# USB.net
KiCad netlist of a schematic drawn in Altium Designer
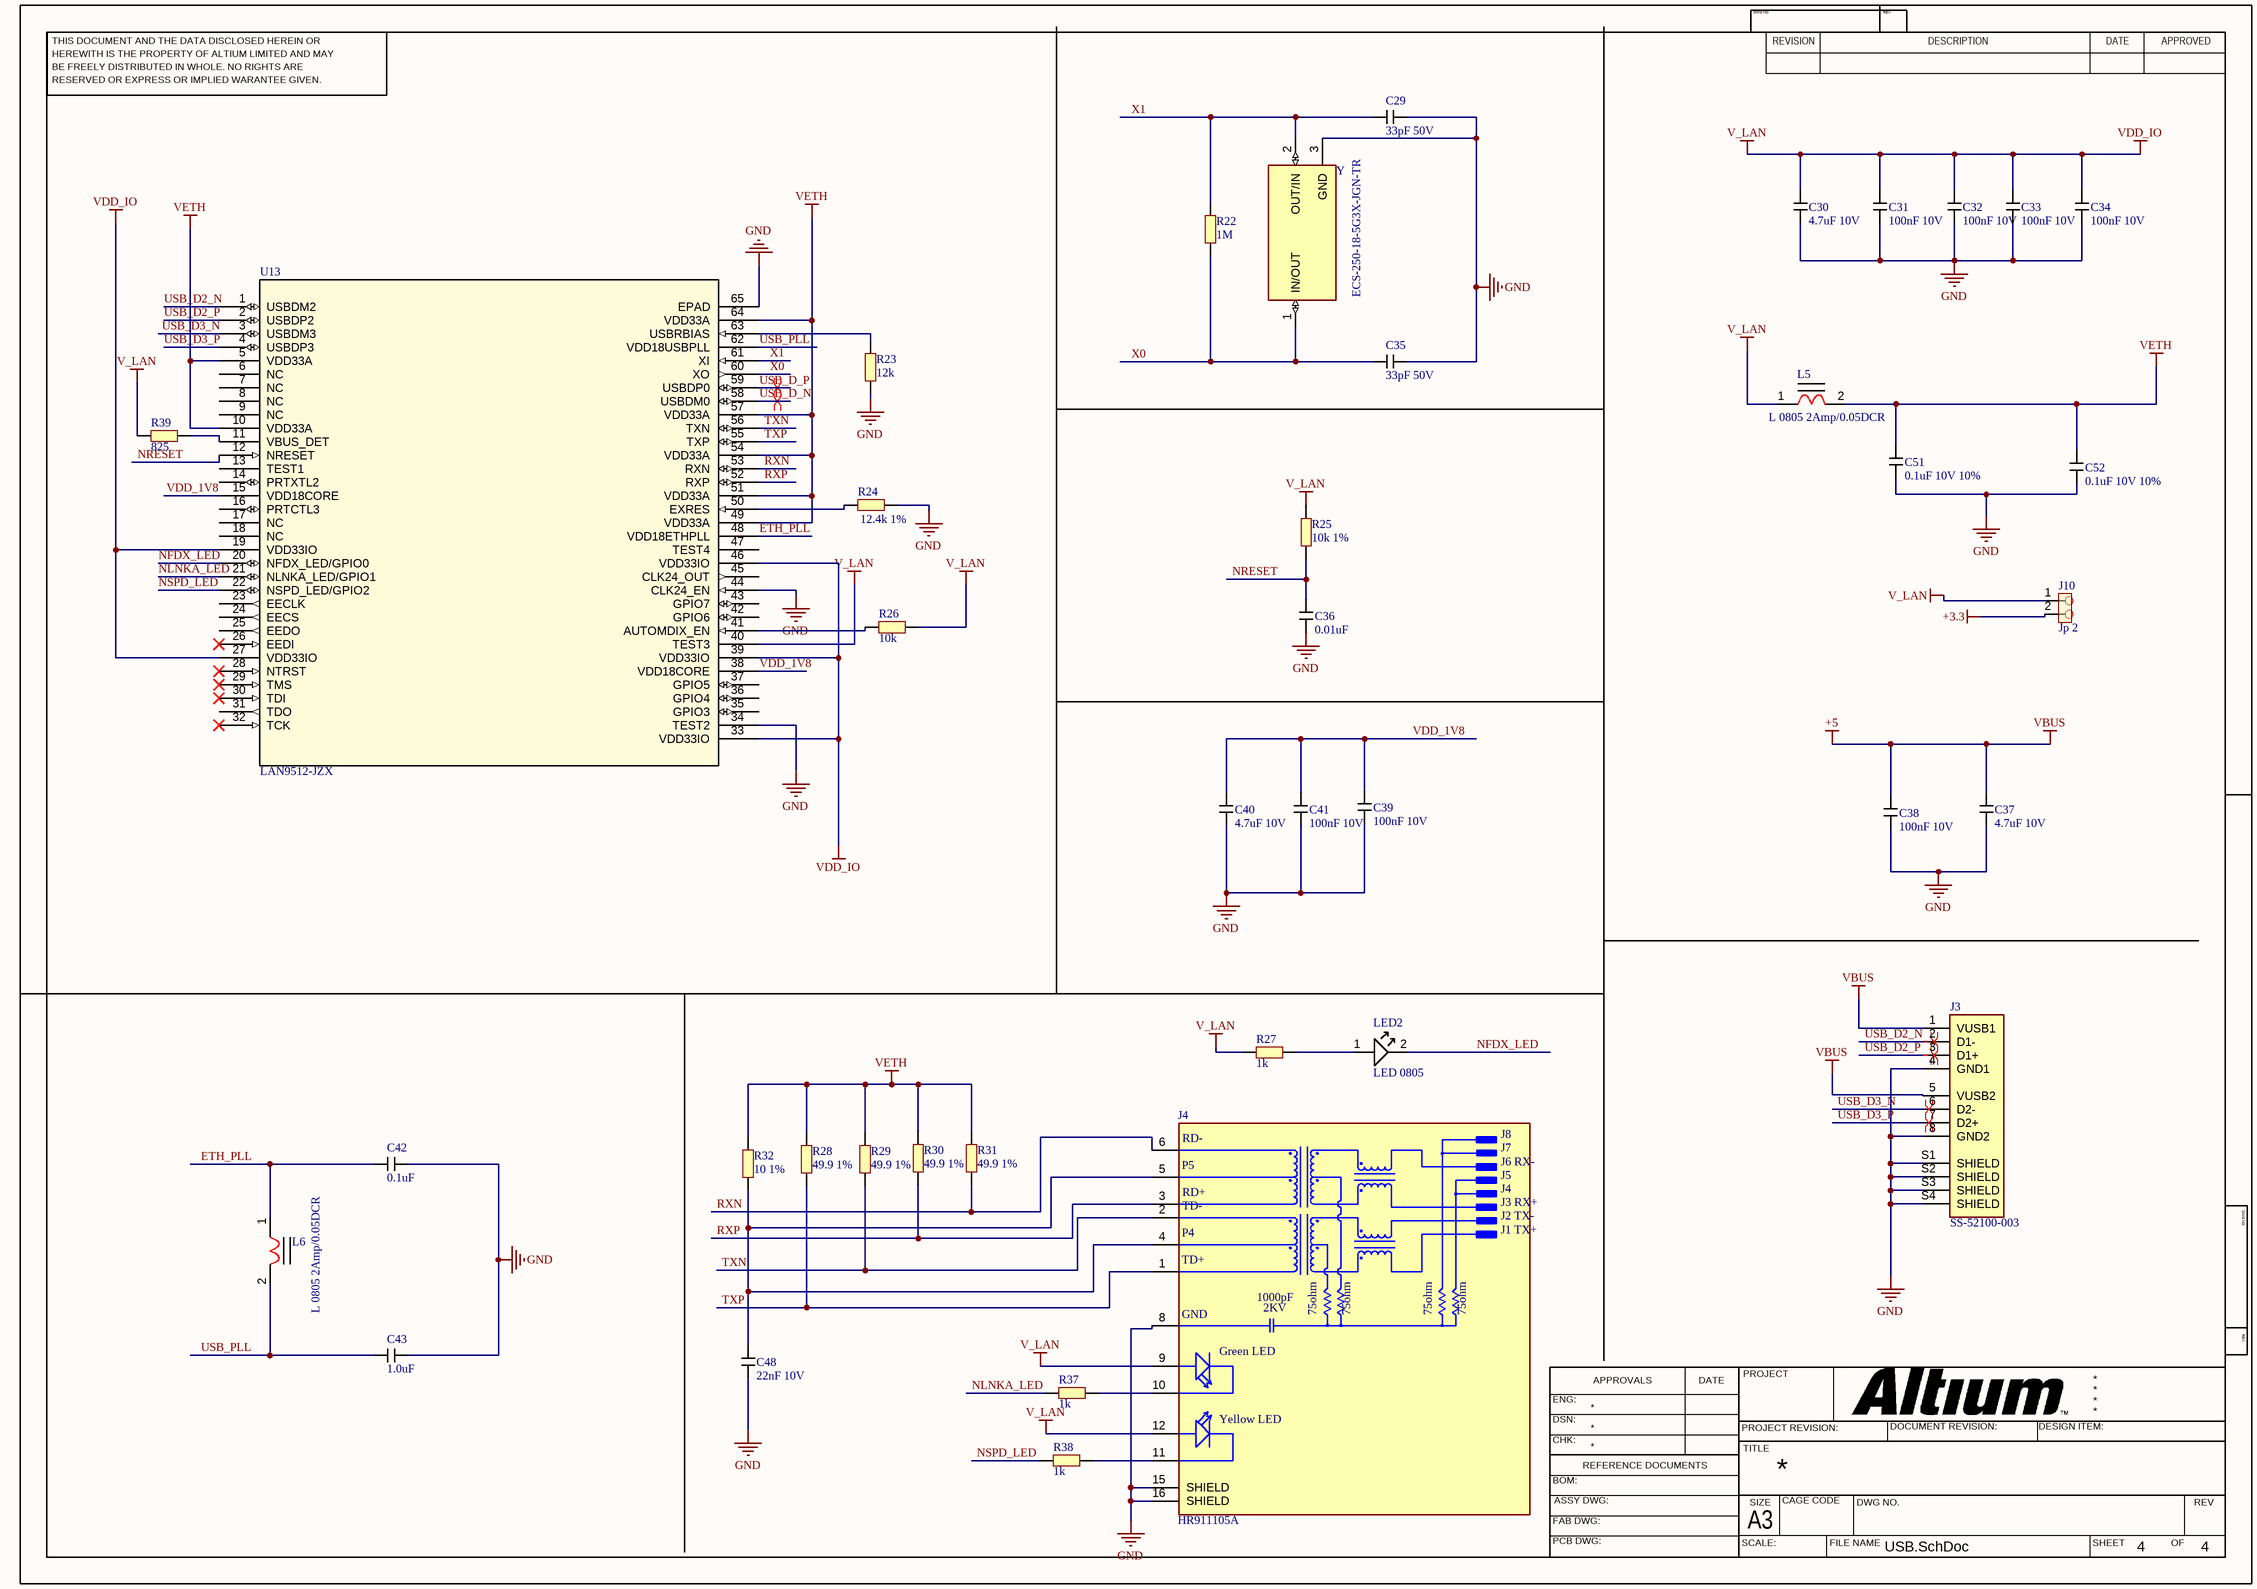
[diagram p0: USB.SchDoc]

(export (version "E")
  (design (tool "Eeschema 10.0.6"))
  (components
    (comp (ref "C29") (value "33pF 50V") (footprint "c 0805") (libsource (lib "NAVISTAR") (part "C 0805")))
    (comp (ref "C30") (value "4.7uF 10V") (footprint "c 0805") (libsource (lib "NAVISTAR") (part "C 0805")))
    (comp (ref "C31") (value "100nF 10V") (footprint "c 0805") (libsource (lib "NAVISTAR") (part "C 0805")))
    (comp (ref "C32") (value "100nF 10V") (footprint "c 0805") (libsource (lib "NAVISTAR") (part "C 0805")))
    (comp (ref "C33") (value "100nF 10V") (footprint "c 0805") (libsource (lib "NAVISTAR") (part "C 0805")))
    (comp (ref "C34") (value "100nF 10V") (footprint "c 0805") (libsource (lib "NAVISTAR") (part "C 0805")))
    (comp (ref "C35") (value "33pF 50V") (footprint "c 0805") (libsource (lib "NAVISTAR") (part "C 0805")))
    (comp (ref "C36") (value "0.01uF") (footprint "c 0805") (libsource (lib "NAVISTAR") (part "C 0805")))
    (comp (ref "C37") (value "4.7uF 10V") (footprint "c 0805") (libsource (lib "NAVISTAR") (part "C 0805")))
    (comp (ref "C38") (value "100nF 10V") (footprint "c 0805") (libsource (lib "NAVISTAR") (part "C 0805")))
    (comp (ref "C39") (value "100nF 10V") (footprint "c 0805") (libsource (lib "NAVISTAR") (part "C 0805")))
    (comp (ref "C40") (value "4.7uF 10V") (footprint "c 0805") (libsource (lib "NAVISTAR") (part "C 0805")))
    (comp (ref "C41") (value "100nF 10V") (footprint "c 0805") (libsource (lib "NAVISTAR") (part "C 0805")))
    (comp (ref "C42") (value "0.1uF") (footprint "c 0805") (libsource (lib "NAVISTAR") (part "C 0805")))
    (comp (ref "C43") (value "1.0uF") (footprint "c 0805") (libsource (lib "NAVISTAR") (part "C 0805")))
    (comp (ref "C48") (value "22nF 10V") (footprint "c 0805") (libsource (lib "Lab1") (part "C 0805")))
    (comp (ref "C51")
      (value "0.1uF 10V 10%")
      (footprint "c 0805")
      (libsource (lib "NAVISTAR") (part "C 0805"))
    )
    (comp (ref "C52")
      (value "0.1uF 10V 10%")
      (footprint "c 0805")
      (libsource (lib "NAVISTAR") (part "C 0805"))
    )
    (comp (ref "J3")
      (value "SS-52100-003")
      (footprint "BEL_SS-52100-003")
      (description "USB 2.0 - A Connector ¦ 2 Port ¦ Stacked Right Angle Receptacle ¦ Shielded")
      (fields (field (name "DIGI-KEY_PART_NUMBER") "380-1414-ND") (field (name "MF") "Stewart Connector"))
      (libsource (lib "SS-52100-003") (part "SS-52100-003"))
    )
    (comp (ref "J4")
      (value "HR911105A")
      (footprint "HANRUN_HR911105A")
      (description "DIP RJ45 Connector;")
      (fields (field (name "MF") "hanrun"))
      (libsource (lib "HR911105A") (part "HR911105A"))
    )
    (comp (ref "J10") (value "Jp 2") (footprint "Jp2") (libsource (lib "NAVISTAR") (part "Jp 2")))
    (comp (ref "L5")
      (value "L 0805 2Amp/0.05DCR")
      (footprint "Ferrite 0805")
      (libsource (lib "NAVISTAR") (part "Ferite 0805"))
    )
    (comp (ref "L6")
      (value "L 0805 2Amp/0.05DCR")
      (footprint "Ferrite 0805")
      (libsource (lib "NAVISTAR") (part "Ferite 0805"))
    )
    (comp (ref "LED2")
      (value "LED 0805")
      (footprint "LED 0805")
      (libsource (lib "NAVISTAR") (part "LED 0805"))
    )
    (comp (ref "R22") (value "1M") (footprint "R 0805") (libsource (lib "") (part "R 0805_1")))
    (comp (ref "R23") (value "12k") (footprint "R 0805") (libsource (lib "") (part "R 0805_1")))
    (comp (ref "R24") (value "12.4k 1%") (footprint "R 0805") (libsource (lib "NAVISTAR") (part "R 0805")))
    (comp (ref "R25") (value "10k 1%") (footprint "R 0805") (libsource (lib "") (part "R 0805_1")))
    (comp (ref "R26") (value "10k") (footprint "R 0805") (libsource (lib "NAVISTAR") (part "R 0805")))
    (comp (ref "R27") (value "1k") (footprint "R 0805") (libsource (lib "NAVISTAR") (part "R 0805")))
    (comp (ref "R28") (value "49.9 1%") (footprint "R 0805") (libsource (lib "") (part "R 0805_1")))
    (comp (ref "R29") (value "49.9 1%") (footprint "R 0805") (libsource (lib "") (part "R 0805_1")))
    (comp (ref "R30") (value "49.9 1%") (footprint "R 0805") (libsource (lib "") (part "R 0805_1")))
    (comp (ref "R31") (value "49.9 1%") (footprint "R 0805") (libsource (lib "") (part "R 0805_1")))
    (comp (ref "R32") (value "10 1%") (footprint "R 0805") (libsource (lib "") (part "R 0805_1")))
    (comp (ref "R37") (value "1k") (footprint "R 0805") (libsource (lib "NAVISTAR") (part "R 0805")))
    (comp (ref "R38") (value "1k") (footprint "R 0805") (libsource (lib "NAVISTAR") (part "R 0805")))
    (comp (ref "R39") (value "825") (footprint "R 0805") (libsource (lib "NAVISTAR") (part "R 0805")))
    (comp (ref "U13")
      (value "LAN9512-JZX")
      (footprint "QFN50P900X900X100-65N-D")
      (description "No Description Available")
      (fields
        (field (name "MANUFACTURER_PART_NUMBER") "LAN9512-JZX-TR")
        (field (name "COPYRIGHT") "Copyright (C) 2023 Ultra Librarian. All rights reserved.")
      )
      (libsource (lib "LAN9512-JZX-TR") (part "LAN9512-JZX-TR"))
    )
    (comp (ref "Y")
      (value "ECS-250-18-5G3X-JGN-TR")
      (footprint "XTAL_ECS-250-18-5G3X-JGN-TR")
      (description "25MHz Â±20ppm Crystal 18pF 30 Ohms HC-49/US")
      (fields (field (name "MF") "ECS Inc."))
      (libsource (lib "ECS-250-18-5G3X-JGN-TR") (part "ECS-250-18-5G3X-JGN-TR"))
    )
  )
  (nets
    (net (code "1") (name "+3.3") (class "Default") (node (ref "J10") (pin "2") (pintype "passive")))
    (net (code "2") (name "+5") (class "Default")
      (node (ref "C37") (pin "2") (pintype "passive"))
      (node (ref "C38") (pin "1") (pintype "passive"))
      (node (ref "J3") (pin "1") (pinfunction "VUSB1_1") (pintype "passive"))
      (node (ref "J3") (pin "5") (pinfunction "VUSB2_5") (pintype "passive"))
    )
    (net (code "3") (name "/ETH_PLL") (class "Default")
      (node (ref "C42") (pin "1") (pintype "passive"))
      (node (ref "L6") (pin "1") (pintype "passive"))
      (node (ref "U13") (pin "48") (pinfunction "VDD18ETHPLL_48") (pintype "power_in"))
    )
    (net (code "4") (name "/NFDX_LED") (class "Default")
      (node (ref "LED2") (pin "2") (pintype "passive"))
      (node (ref "U13") (pin "20") (pinfunction "NFDX_LED/GPIO0_20") (pintype "bidirectional"))
    )
    (net (code "5") (name "/NLNKA_LED") (class "Default")
      (node (ref "R37") (pin "1") (pintype "passive"))
      (node (ref "U13") (pin "21") (pinfunction "NLNKA_LED/GPIO1_21") (pintype "bidirectional"))
    )
    (net (code "6") (name "/NRESET") (class "Default")
      (node (ref "C36") (pin "2") (pintype "passive"))
      (node (ref "R25") (pin "1") (pintype "passive"))
      (node (ref "U13") (pin "12") (pinfunction "NRESET_12") (pintype "input"))
    )
    (net (code "7") (name "/NSPD_LED") (class "Default")
      (node (ref "R38") (pin "1") (pintype "passive"))
      (node (ref "U13") (pin "22") (pinfunction "NSPD_LED/GPIO2_22") (pintype "bidirectional"))
    )
    (net (code "8") (name "/RXN") (class "Default")
      (node (ref "J4") (pin "6") (pinfunction "RD-_6") (pintype "passive"))
      (node (ref "R31") (pin "1") (pintype "passive"))
      (node (ref "U13") (pin "53") (pinfunction "RXN_53") (pintype "bidirectional"))
    )
    (net (code "9") (name "/RXP") (class "Default")
      (node (ref "J4") (pin "3") (pinfunction "RD+_3") (pintype "passive"))
      (node (ref "R30") (pin "1") (pintype "passive"))
      (node (ref "U13") (pin "52") (pinfunction "RXP_52") (pintype "bidirectional"))
    )
    (net (code "10") (name "/TXN") (class "Default")
      (node (ref "J4") (pin "2") (pinfunction "TD-_2") (pintype "passive"))
      (node (ref "R29") (pin "1") (pintype "passive"))
      (node (ref "U13") (pin "56") (pinfunction "TXN_56") (pintype "bidirectional"))
    )
    (net (code "11") (name "/TXP") (class "Default")
      (node (ref "J4") (pin "1") (pinfunction "TD+_1") (pintype "passive"))
      (node (ref "R28") (pin "1") (pintype "passive"))
      (node (ref "U13") (pin "55") (pinfunction "TXP_55") (pintype "bidirectional"))
    )
    (net (code "12") (name "/USB_D2_N") (class "Default")
      (node (ref "J3") (pin "2") (pinfunction "D1-_2") (pintype "passive"))
      (node (ref "U13") (pin "1") (pinfunction "USBDM2_1") (pintype "bidirectional"))
    )
    (net (code "13") (name "/USB_D2_P") (class "Default")
      (node (ref "J3") (pin "3") (pinfunction "D1+_3") (pintype "passive"))
      (node (ref "U13") (pin "2") (pinfunction "USBDP2_2") (pintype "bidirectional"))
    )
    (net (code "14") (name "/USB_D3_N") (class "Default")
      (node (ref "J3") (pin "6") (pinfunction "D2-_6") (pintype "passive"))
      (node (ref "U13") (pin "3") (pinfunction "USBDM3_3") (pintype "bidirectional"))
    )
    (net (code "15") (name "/USB_D3_P") (class "Default")
      (node (ref "J3") (pin "7") (pinfunction "D2+_7") (pintype "passive"))
      (node (ref "U13") (pin "4") (pinfunction "USBDP3_4") (pintype "bidirectional"))
    )
    (net (code "16") (name "/USB_D_N") (class "Default")
      (node (ref "U13") (pin "58") (pinfunction "USBDM0_58") (pintype "bidirectional"))
    )
    (net (code "17") (name "/USB_D_P") (class "Default")
      (node (ref "U13") (pin "59") (pinfunction "USBDP0_59") (pintype "bidirectional"))
    )
    (net (code "18") (name "/USB_PLL") (class "Default")
      (node (ref "C43") (pin "2") (pintype "passive"))
      (node (ref "L6") (pin "2") (pintype "passive"))
      (node (ref "U13") (pin "62") (pinfunction "VDD18USBPLL_62") (pintype "power_in"))
    )
    (net (code "19") (name "/VDD_1V8") (class "Default")
      (node (ref "C39") (pin "2") (pintype "passive"))
      (node (ref "C40") (pin "2") (pintype "passive"))
      (node (ref "C41") (pin "2") (pintype "passive"))
      (node (ref "U13") (pin "15") (pinfunction "VDD18CORE_15") (pintype "power_in"))
      (node (ref "U13") (pin "38") (pinfunction "VDD18CORE_38") (pintype "power_in"))
    )
    (net (code "20") (name "/X0") (class "Default")
      (node (ref "C35") (pin "1") (pintype "passive"))
      (node (ref "R22") (pin "1") (pintype "passive"))
      (node (ref "U13") (pin "60") (pinfunction "XO_60") (pintype "output"))
      (node (ref "Y") (pin "1") (pinfunction "IN/OUT_1") (pintype "bidirectional"))
    )
    (net (code "21") (name "/X1") (class "Default")
      (node (ref "C29") (pin "1") (pintype "passive"))
      (node (ref "R22") (pin "2") (pintype "passive"))
      (node (ref "U13") (pin "61") (pinfunction "XI_61") (pintype "input"))
      (node (ref "Y") (pin "2") (pinfunction "OUT/IN_2") (pintype "bidirectional"))
    )
    (net (code "22") (name "GND") (class "Default")
      (node (ref "C29") (pin "2") (pintype "passive"))
      (node (ref "C30") (pin "1") (pintype "passive"))
      (node (ref "C31") (pin "1") (pintype "passive"))
      (node (ref "C32") (pin "1") (pintype "passive"))
      (node (ref "C33") (pin "1") (pintype "passive"))
      (node (ref "C34") (pin "1") (pintype "passive"))
      (node (ref "C35") (pin "2") (pintype "passive"))
      (node (ref "C36") (pin "1") (pintype "passive"))
      (node (ref "C37") (pin "1") (pintype "passive"))
      (node (ref "C38") (pin "2") (pintype "passive"))
      (node (ref "C39") (pin "1") (pintype "passive"))
      (node (ref "C40") (pin "1") (pintype "passive"))
      (node (ref "C41") (pin "1") (pintype "passive"))
      (node (ref "C42") (pin "2") (pintype "passive"))
      (node (ref "C43") (pin "1") (pintype "passive"))
      (node (ref "C48") (pin "2") (pintype "passive"))
      (node (ref "C51") (pin "1") (pintype "passive"))
      (node (ref "C52") (pin "1") (pintype "passive"))
      (node (ref "J3") (pin "4") (pinfunction "GND1_4") (pintype "passive"))
      (node (ref "J3") (pin "8") (pinfunction "GND2_8") (pintype "passive"))
      (node (ref "J3") (pin "S1") (pinfunction "SHIELD_S1") (pintype "passive"))
      (node (ref "J3") (pin "S2") (pinfunction "SHIELD_S2") (pintype "passive"))
      (node (ref "J3") (pin "S3") (pinfunction "SHIELD_S3") (pintype "passive"))
      (node (ref "J3") (pin "S4") (pinfunction "SHIELD_S4") (pintype "passive"))
      (node (ref "J4") (pin "15") (pinfunction "SHIELD_15") (pintype "passive"))
      (node (ref "J4") (pin "16") (pinfunction "SHIELD_16") (pintype "passive"))
      (node (ref "J4") (pin "8") (pinfunction "GND_8") (pintype "power_in"))
      (node (ref "R23") (pin "1") (pintype "passive"))
      (node (ref "R24") (pin "2") (pintype "passive"))
      (node (ref "U13") (pin "34") (pinfunction "TEST2_34") (pintype "passive"))
      (node (ref "U13") (pin "44") (pinfunction "CLK24_EN_44") (pintype "input"))
      (node (ref "U13") (pin "65") (pinfunction "EPAD_65") (pintype "passive"))
      (node (ref "Y") (pin "3") (pinfunction "GND_3") (pintype "power_in"))
    )
    (net (code "23") (name "Net-(J4-GC)") (class "Default")
      (node (ref "J4") (pin "10") (pinfunction "GC_10") (pintype "passive"))
      (node (ref "R37") (pin "2") (pintype "passive"))
    )
    (net (code "24") (name "Net-(J4-P4)") (class "Default")
      (node (ref "C48") (pin "1") (pintype "passive"))
      (node (ref "J4") (pin "4") (pinfunction "P4_4") (pintype "passive"))
      (node (ref "J4") (pin "5") (pinfunction "P5_5") (pintype "passive"))
      (node (ref "R32") (pin "1") (pintype "passive"))
    )
    (net (code "25") (name "Net-(J4-YC)") (class "Default")
      (node (ref "J4") (pin "11") (pinfunction "YC_11") (pintype "passive"))
      (node (ref "R38") (pin "2") (pintype "passive"))
    )
    (net (code "26") (name "Net-(LED2-Pad1)") (class "Default")
      (node (ref "LED2") (pin "1") (pintype "passive"))
      (node (ref "R27") (pin "2") (pintype "passive"))
    )
    (net (code "27") (name "Net-(U13-AUTOMDIX_EN)") (class "Default")
      (node (ref "R26") (pin "1") (pintype "passive"))
      (node (ref "U13") (pin "41") (pinfunction "AUTOMDIX_EN_41") (pintype "input"))
    )
    (net (code "28") (name "Net-(U13-EXRES)") (class "Default")
      (node (ref "R24") (pin "1") (pintype "passive"))
      (node (ref "U13") (pin "50") (pinfunction "EXRES_50") (pintype "input"))
    )
    (net (code "29") (name "Net-(U13-USBRBIAS)") (class "Default")
      (node (ref "R23") (pin "2") (pintype "passive"))
      (node (ref "U13") (pin "63") (pinfunction "USBRBIAS_63") (pintype "input"))
    )
    (net (code "30") (name "Net-(U13-VBUS_DET)") (class "Default")
      (node (ref "R39") (pin "2") (pintype "passive"))
      (node (ref "U13") (pin "11") (pinfunction "VBUS_DET_11") (pintype "power_in"))
    )
    (net (code "31") (name "VDD_IO") (class "Default")
      (node (ref "C30") (pin "2") (pintype "passive"))
      (node (ref "C31") (pin "2") (pintype "passive"))
      (node (ref "C32") (pin "2") (pintype "passive"))
      (node (ref "C33") (pin "2") (pintype "passive"))
      (node (ref "C34") (pin "2") (pintype "passive"))
      (node (ref "J10") (pin "1") (pintype "passive"))
      (node (ref "J4") (pin "12") (pinfunction "YA_12") (pintype "passive"))
      (node (ref "J4") (pin "9") (pinfunction "GA_9") (pintype "passive"))
      (node (ref "L5") (pin "1") (pintype "passive"))
      (node (ref "R25") (pin "2") (pintype "passive"))
      (node (ref "R26") (pin "2") (pintype "passive"))
      (node (ref "R27") (pin "1") (pintype "passive"))
      (node (ref "R39") (pin "1") (pintype "passive"))
      (node (ref "U13") (pin "19") (pinfunction "VDD33IO_19") (pintype "power_in"))
      (node (ref "U13") (pin "27") (pinfunction "VDD33IO_27") (pintype "power_in"))
      (node (ref "U13") (pin "33") (pinfunction "VDD33IO_33") (pintype "power_in"))
      (node (ref "U13") (pin "39") (pinfunction "VDD33IO_39") (pintype "power_in"))
      (node (ref "U13") (pin "40") (pinfunction "TEST3_40") (pintype "passive"))
      (node (ref "U13") (pin "46") (pinfunction "VDD33IO_46") (pintype "power_in"))
    )
    (net (code "32") (name "VETH") (class "Default")
      (node (ref "C51") (pin "2") (pintype "passive"))
      (node (ref "C52") (pin "2") (pintype "passive"))
      (node (ref "L5") (pin "2") (pintype "passive"))
      (node (ref "R28") (pin "2") (pintype "passive"))
      (node (ref "R29") (pin "2") (pintype "passive"))
      (node (ref "R30") (pin "2") (pintype "passive"))
      (node (ref "R31") (pin "2") (pintype "passive"))
      (node (ref "R32") (pin "2") (pintype "passive"))
      (node (ref "U13") (pin "10") (pinfunction "VDD33A_10") (pintype "power_in"))
      (node (ref "U13") (pin "49") (pinfunction "VDD33A_49") (pintype "power_in"))
      (node (ref "U13") (pin "5") (pinfunction "VDD33A_5") (pintype "power_in"))
      (node (ref "U13") (pin "51") (pinfunction "VDD33A_51") (pintype "power_in"))
      (node (ref "U13") (pin "54") (pinfunction "VDD33A_54") (pintype "power_in"))
      (node (ref "U13") (pin "57") (pinfunction "VDD33A_57") (pintype "power_in"))
      (node (ref "U13") (pin "64") (pinfunction "VDD33A_64") (pintype "power_in"))
    )
    (net (code "33") (name "unconnected-(U13-CLK24_OUT-Pad45)") (class "Default")
      (node (ref "U13") (pin "45") (pinfunction "CLK24_OUT_45") (pintype "output"))
    )
    (net (code "34") (name "unconnected-(U13-EECLK-Pad23)") (class "Default")
      (node (ref "U13") (pin "23") (pinfunction "EECLK_23") (pintype "output"))
    )
    (net (code "35") (name "unconnected-(U13-EECS-Pad24)") (class "Default")
      (node (ref "U13") (pin "24") (pinfunction "EECS_24") (pintype "output"))
    )
    (net (code "36") (name "unconnected-(U13-EEDI-Pad26)") (class "Default")
      (node (ref "U13") (pin "26") (pinfunction "EEDI_26") (pintype "input+no_connect"))
    )
    (net (code "37") (name "unconnected-(U13-EEDO-Pad25)") (class "Default")
      (node (ref "U13") (pin "25") (pinfunction "EEDO_25") (pintype "output"))
    )
    (net (code "38") (name "unconnected-(U13-GPIO3-Pad35)") (class "Default")
      (node (ref "U13") (pin "35") (pinfunction "GPIO3_35") (pintype "bidirectional"))
    )
    (net (code "39") (name "unconnected-(U13-GPIO4-Pad36)") (class "Default")
      (node (ref "U13") (pin "36") (pinfunction "GPIO4_36") (pintype "bidirectional"))
    )
    (net (code "40") (name "unconnected-(U13-GPIO5-Pad37)") (class "Default")
      (node (ref "U13") (pin "37") (pinfunction "GPIO5_37") (pintype "bidirectional"))
    )
    (net (code "41") (name "unconnected-(U13-GPIO6-Pad42)") (class "Default")
      (node (ref "U13") (pin "42") (pinfunction "GPIO6_42") (pintype "bidirectional"))
    )
    (net (code "42") (name "unconnected-(U13-GPIO7-Pad43)") (class "Default")
      (node (ref "U13") (pin "43") (pinfunction "GPIO7_43") (pintype "bidirectional"))
    )
    (net (code "43") (name "unconnected-(U13-NC-Pad6)") (class "Default")
      (node (ref "U13") (pin "6") (pinfunction "NC_6") (pintype "passive"))
    )
    (net (code "44") (name "unconnected-(U13-NC-Pad7)") (class "Default")
      (node (ref "U13") (pin "7") (pinfunction "NC_7") (pintype "passive"))
    )
    (net (code "45") (name "unconnected-(U13-NC-Pad8)") (class "Default")
      (node (ref "U13") (pin "8") (pinfunction "NC_8") (pintype "passive"))
    )
    (net (code "46") (name "unconnected-(U13-NC-Pad9)") (class "Default")
      (node (ref "U13") (pin "9") (pinfunction "NC_9") (pintype "passive"))
    )
    (net (code "47") (name "unconnected-(U13-NC-Pad17)") (class "Default")
      (node (ref "U13") (pin "17") (pinfunction "NC_17") (pintype "passive"))
    )
    (net (code "48") (name "unconnected-(U13-NC-Pad18)") (class "Default")
      (node (ref "U13") (pin "18") (pinfunction "NC_18") (pintype "passive"))
    )
    (net (code "49") (name "unconnected-(U13-NTRST-Pad28)") (class "Default")
      (node (ref "U13") (pin "28") (pinfunction "NTRST_28") (pintype "input+no_connect"))
    )
    (net (code "50") (name "unconnected-(U13-PRTCTL3-Pad16)") (class "Default")
      (node (ref "U13") (pin "16") (pinfunction "PRTCTL3_16") (pintype "bidirectional"))
    )
    (net (code "51") (name "unconnected-(U13-PRTXTL2-Pad14)") (class "Default")
      (node (ref "U13") (pin "14") (pinfunction "PRTXTL2_14") (pintype "bidirectional"))
    )
    (net (code "52") (name "unconnected-(U13-TCK-Pad32)") (class "Default")
      (node (ref "U13") (pin "32") (pinfunction "TCK_32") (pintype "input+no_connect"))
    )
    (net (code "53") (name "unconnected-(U13-TDI-Pad30)") (class "Default")
      (node (ref "U13") (pin "30") (pinfunction "TDI_30") (pintype "input+no_connect"))
    )
    (net (code "54") (name "unconnected-(U13-TDO-Pad31)") (class "Default")
      (node (ref "U13") (pin "31") (pinfunction "TDO_31") (pintype "output"))
    )
    (net (code "55") (name "unconnected-(U13-TEST1-Pad13)") (class "Default")
      (node (ref "U13") (pin "13") (pinfunction "TEST1_13") (pintype "passive"))
    )
    (net (code "56") (name "unconnected-(U13-TEST4-Pad47)") (class "Default")
      (node (ref "U13") (pin "47") (pinfunction "TEST4_47") (pintype "passive"))
    )
    (net (code "57") (name "unconnected-(U13-TMS-Pad29)") (class "Default")
      (node (ref "U13") (pin "29") (pinfunction "TMS_29") (pintype "input+no_connect"))
    )
  )
)
